# 11_-TFT-Interface.net
KiCad netlist of a schematic drawn in Altium Designer
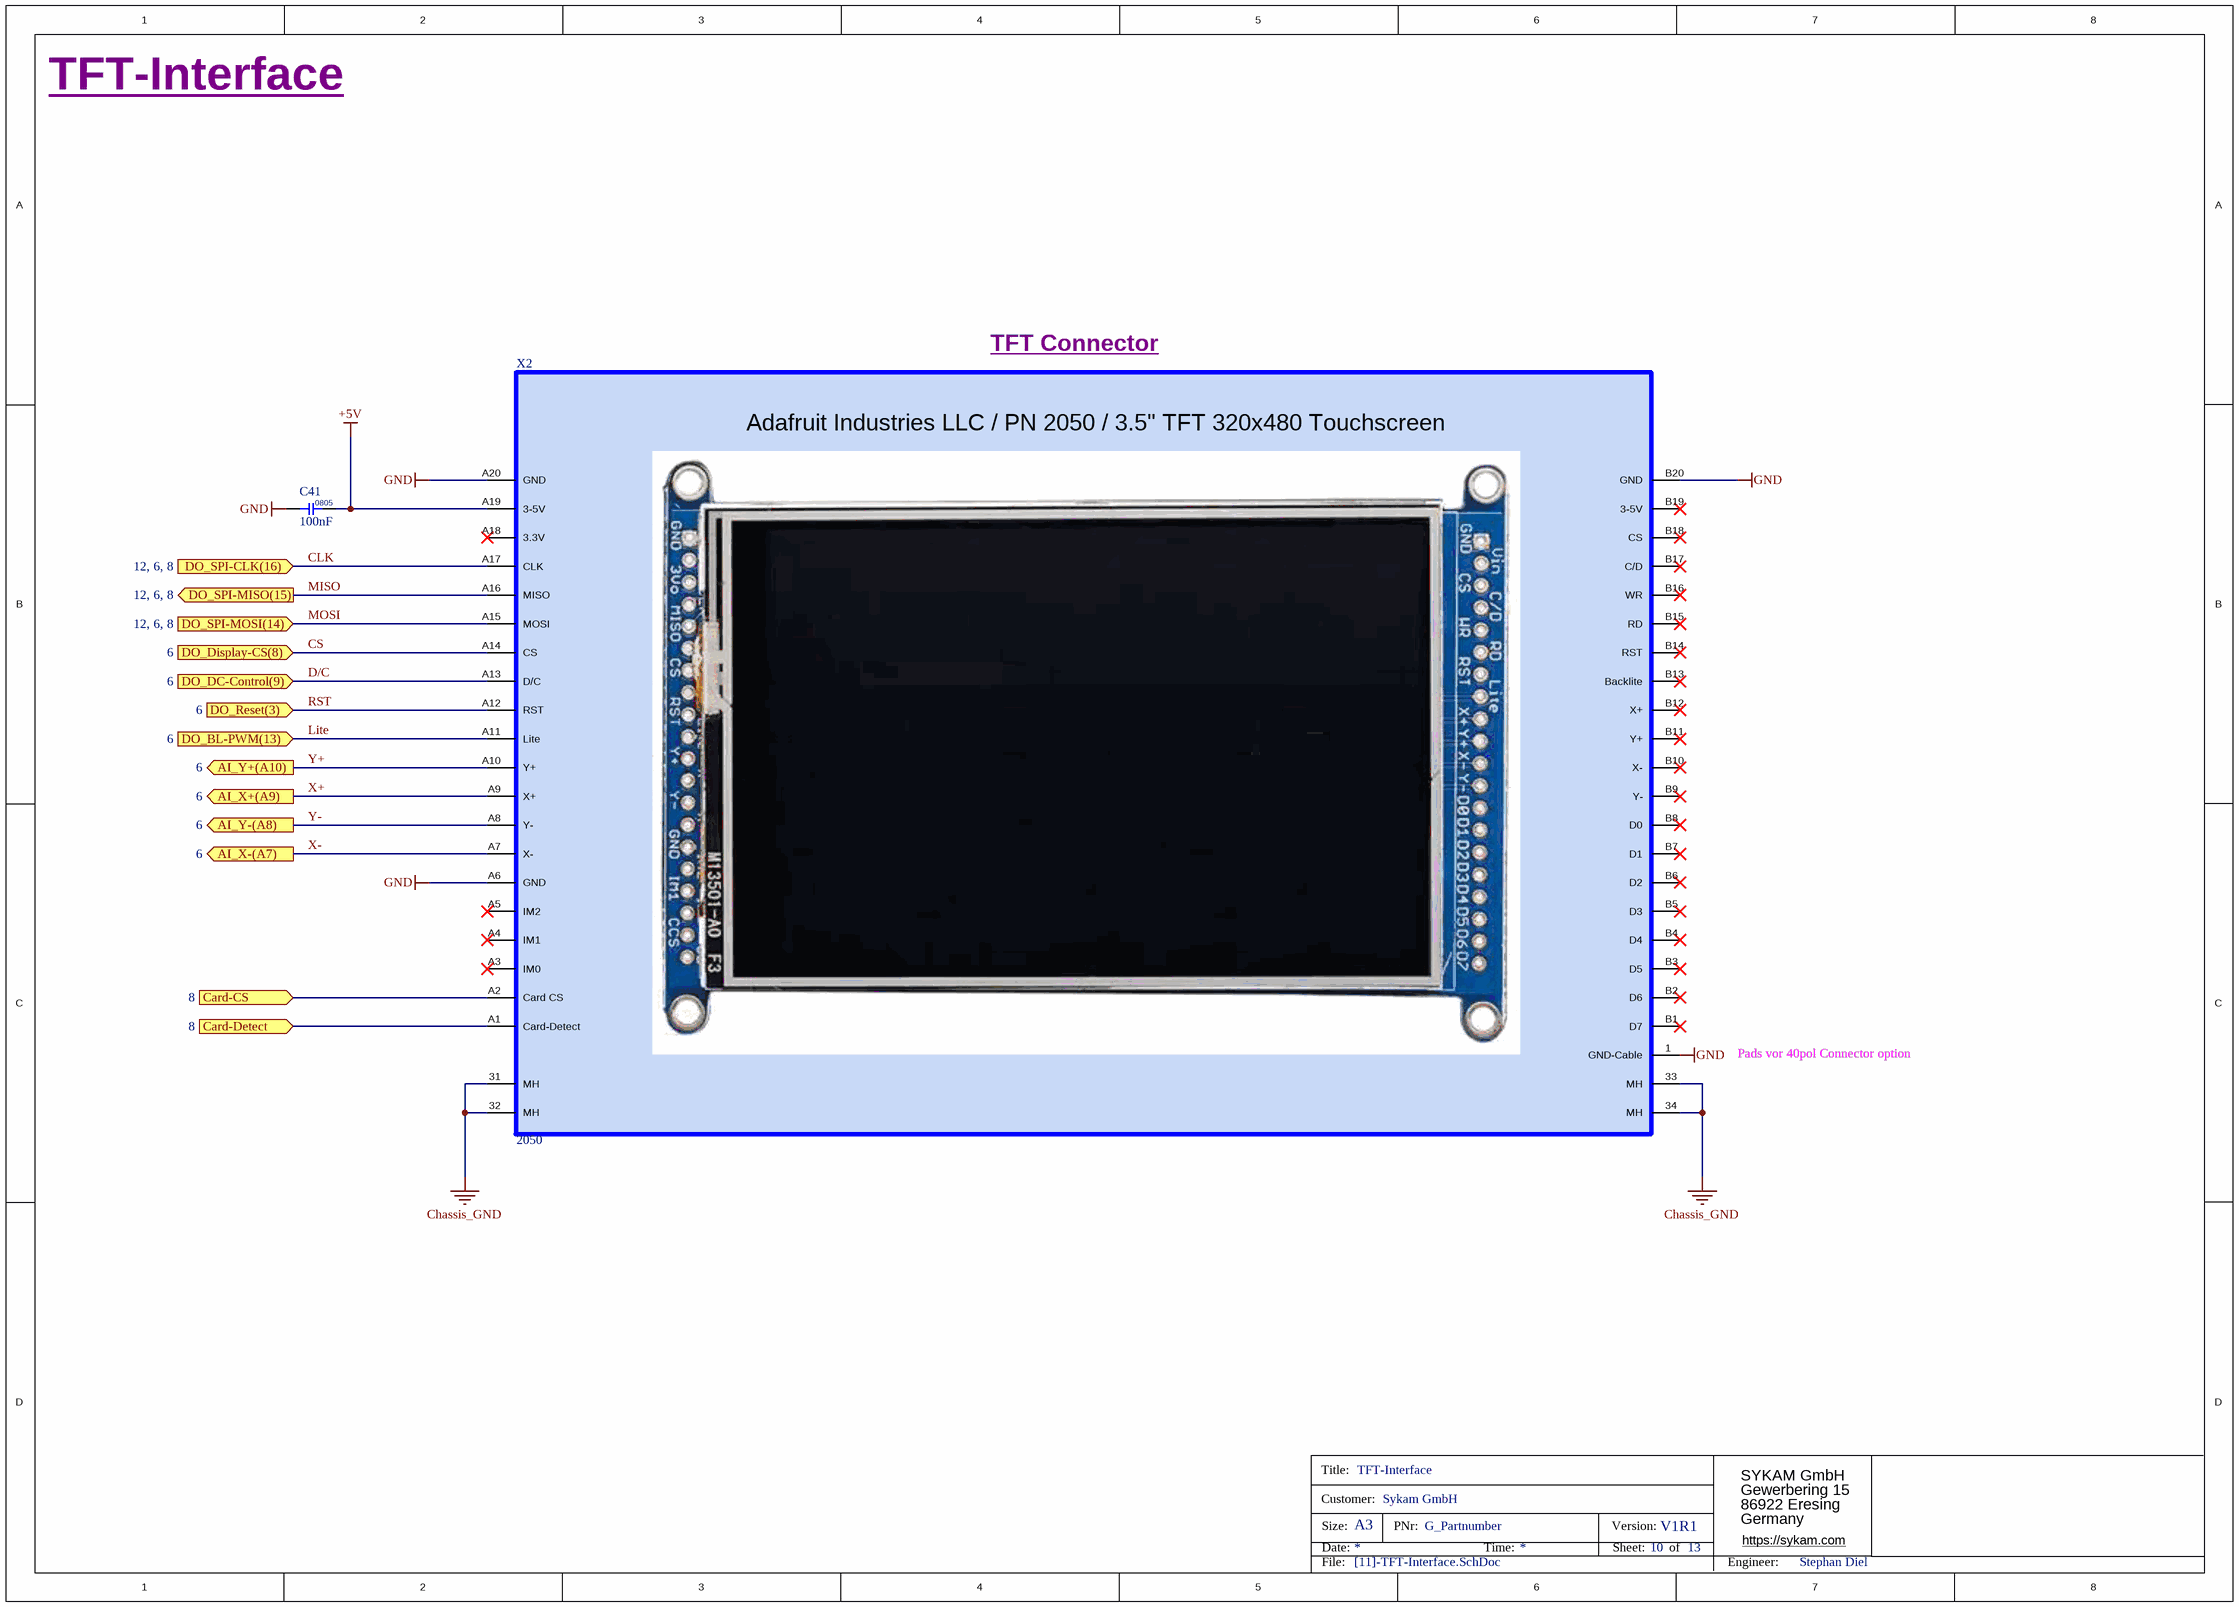
[diagram p0: [11]-TFT-Interface.SchDoc]

(export (version "E")
  (design (tool "Eeschema 10.0.6"))
  (components
    (comp (ref "C41")
      (value "100nF")
      (footprint "C0805")
      (description "CAP CER 0.1UF 50V X7R 0805")
      (fields
        (field (name "MANUFACTURER PART NUMBER") "CC0805KRX7R9BB104")
        (field (name "TOLERANCE") "10%")
        (field (name "PCBCHECKED") "initials after Checked")
        (field (name "SCHCHECKED") "Initials after checked")
      )
      (libsource (lib "ToradexMainBoard-V0I1") (part "C_100nF_CC0805KRX7R9BB104"))
    )
    (comp (ref "X2")
      (value "2050")
      (footprint "CON_Adafruit35-TFT")
      (description "3.5\" TFT 320X480 TOUCHSCREEN")
      (fields (field (name "MANUFACTURER") "Adafruit Industries"))
      (libsource (lib "ToradexMainBoard-V0I1") (part "CON_Modul-TFT-3.5in_2050"))
    )
  )
  (nets
    (net (code "1") (name "+5V") (class "Default")
      (node (ref "C41") (pin "2") (pinfunction "2_2") (pintype "passive"))
      (node (ref "X2") (pin "A19") (pinfunction "3-5V_A19") (pintype "passive"))
    )
    (net (code "2") (name "/CLK") (class "Default")
      (node (ref "X2") (pin "A17") (pinfunction "CLK_A17") (pintype "passive"))
    )
    (net (code "3") (name "/CS") (class "Default")
      (node (ref "X2") (pin "A14") (pinfunction "CS_A14") (pintype "passive"))
    )
    (net (code "4") (name "/Card-CS") (class "Default")
      (node (ref "X2") (pin "A2") (pinfunction "Card_CS_A2") (pintype "passive"))
    )
    (net (code "5") (name "/Card-Detect") (class "Default")
      (node (ref "X2") (pin "A1") (pinfunction "Card-Detect_A1") (pintype "passive"))
    )
    (net (code "6") (name "/D{slash}C") (class "Default")
      (node (ref "X2") (pin "A13") (pinfunction "D/C_A13") (pintype "passive"))
    )
    (net (code "7") (name "/Lite") (class "Default")
      (node (ref "X2") (pin "A11") (pinfunction "Lite_A11") (pintype "passive"))
    )
    (net (code "8") (name "/MISO") (class "Default")
      (node (ref "X2") (pin "A16") (pinfunction "MISO_A16") (pintype "passive"))
    )
    (net (code "9") (name "/MOSI") (class "Default")
      (node (ref "X2") (pin "A15") (pinfunction "MOSI_A15") (pintype "passive"))
    )
    (net (code "10") (name "/RST") (class "Default")
      (node (ref "X2") (pin "A12") (pinfunction "RST_A12") (pintype "passive"))
    )
    (net (code "11") (name "/X+") (class "Default")
      (node (ref "X2") (pin "A9") (pinfunction "X+_A9") (pintype "passive"))
    )
    (net (code "12") (name "/X-") (class "Default")
      (node (ref "X2") (pin "A7") (pinfunction "X-_A7") (pintype "passive"))
    )
    (net (code "13") (name "/Y+") (class "Default")
      (node (ref "X2") (pin "A10") (pinfunction "Y+_A10") (pintype "passive"))
    )
    (net (code "14") (name "/Y-") (class "Default")
      (node (ref "X2") (pin "A8") (pinfunction "Y-_A8") (pintype "passive"))
    )
    (net (code "15") (name "Chassis_GND") (class "Default")
      (node (ref "X2") (pin "31") (pinfunction "MH_31") (pintype "passive"))
      (node (ref "X2") (pin "32") (pinfunction "MH_32") (pintype "passive"))
      (node (ref "X2") (pin "33") (pinfunction "MH_33") (pintype "passive"))
      (node (ref "X2") (pin "34") (pinfunction "MH_34") (pintype "passive"))
    )
    (net (code "16") (name "GND") (class "Default")
      (node (ref "C41") (pin "1") (pinfunction "1_1") (pintype "passive"))
      (node (ref "X2") (pin "1") (pinfunction "GND-Cable_1") (pintype "passive"))
      (node (ref "X2") (pin "A20") (pinfunction "GND_A20") (pintype "passive"))
      (node (ref "X2") (pin "A6") (pinfunction "GND_A6") (pintype "passive"))
      (node (ref "X2") (pin "B20") (pinfunction "GND_B20") (pintype "passive"))
    )
    (net (code "17") (name "unconnected-(X2-3-5V-PadB19)") (class "Default")
      (node (ref "X2") (pin "B19") (pinfunction "3-5V_B19") (pintype "passive+no_connect"))
    )
    (net (code "18") (name "unconnected-(X2-3.3V-PadA18)") (class "Default")
      (node (ref "X2") (pin "A18") (pinfunction "3.3V_A18") (pintype "passive+no_connect"))
    )
    (net (code "19") (name "unconnected-(X2-Backlite-PadB13)") (class "Default")
      (node (ref "X2") (pin "B13") (pinfunction "Backlite_B13") (pintype "passive+no_connect"))
    )
    (net (code "20") (name "unconnected-(X2-CS-PadB18)") (class "Default")
      (node (ref "X2") (pin "B18") (pinfunction "CS_B18") (pintype "passive+no_connect"))
    )
    (net (code "21") (name "unconnected-(X2-C{slash}D-PadB17)") (class "Default")
      (node (ref "X2") (pin "B17") (pinfunction "C/D_B17") (pintype "passive+no_connect"))
    )
    (net (code "22") (name "unconnected-(X2-D0-PadB8)") (class "Default")
      (node (ref "X2") (pin "B8") (pinfunction "D0_B8") (pintype "passive+no_connect"))
    )
    (net (code "23") (name "unconnected-(X2-D1-PadB7)") (class "Default")
      (node (ref "X2") (pin "B7") (pinfunction "D1_B7") (pintype "passive+no_connect"))
    )
    (net (code "24") (name "unconnected-(X2-D2-PadB6)") (class "Default")
      (node (ref "X2") (pin "B6") (pinfunction "D2_B6") (pintype "passive+no_connect"))
    )
    (net (code "25") (name "unconnected-(X2-D3-PadB5)") (class "Default")
      (node (ref "X2") (pin "B5") (pinfunction "D3_B5") (pintype "passive+no_connect"))
    )
    (net (code "26") (name "unconnected-(X2-D4-PadB4)") (class "Default")
      (node (ref "X2") (pin "B4") (pinfunction "D4_B4") (pintype "passive+no_connect"))
    )
    (net (code "27") (name "unconnected-(X2-D5-PadB3)") (class "Default")
      (node (ref "X2") (pin "B3") (pinfunction "D5_B3") (pintype "passive+no_connect"))
    )
    (net (code "28") (name "unconnected-(X2-D6-PadB2)") (class "Default")
      (node (ref "X2") (pin "B2") (pinfunction "D6_B2") (pintype "passive+no_connect"))
    )
    (net (code "29") (name "unconnected-(X2-D7-PadB1)") (class "Default")
      (node (ref "X2") (pin "B1") (pinfunction "D7_B1") (pintype "passive+no_connect"))
    )
    (net (code "30") (name "unconnected-(X2-IM0-PadA3)") (class "Default")
      (node (ref "X2") (pin "A3") (pinfunction "IM0_A3") (pintype "passive+no_connect"))
    )
    (net (code "31") (name "unconnected-(X2-IM1-PadA4)") (class "Default")
      (node (ref "X2") (pin "A4") (pinfunction "IM1_A4") (pintype "passive+no_connect"))
    )
    (net (code "32") (name "unconnected-(X2-IM2-PadA5)") (class "Default")
      (node (ref "X2") (pin "A5") (pinfunction "IM2_A5") (pintype "passive+no_connect"))
    )
    (net (code "33") (name "unconnected-(X2-RD-PadB15)") (class "Default")
      (node (ref "X2") (pin "B15") (pinfunction "RD_B15") (pintype "passive+no_connect"))
    )
    (net (code "34") (name "unconnected-(X2-RST-PadB14)") (class "Default")
      (node (ref "X2") (pin "B14") (pinfunction "RST_B14") (pintype "passive+no_connect"))
    )
    (net (code "35") (name "unconnected-(X2-WR-PadB16)") (class "Default")
      (node (ref "X2") (pin "B16") (pinfunction "WR_B16") (pintype "passive+no_connect"))
    )
    (net (code "36") (name "unconnected-(X2-X+-PadB12)") (class "Default")
      (node (ref "X2") (pin "B12") (pinfunction "X+_B12") (pintype "passive+no_connect"))
    )
    (net (code "37") (name "unconnected-(X2-X--PadB10)") (class "Default")
      (node (ref "X2") (pin "B10") (pinfunction "X-_B10") (pintype "passive+no_connect"))
    )
    (net (code "38") (name "unconnected-(X2-Y+-PadB11)") (class "Default")
      (node (ref "X2") (pin "B11") (pinfunction "Y+_B11") (pintype "passive+no_connect"))
    )
    (net (code "39") (name "unconnected-(X2-Y--PadB9)") (class "Default")
      (node (ref "X2") (pin "B9") (pinfunction "Y-_B9") (pintype "passive+no_connect"))
    )
  )
)
